# nigme2_Crocodile.net
KiCad netlist of a schematic drawn in Altium Designer
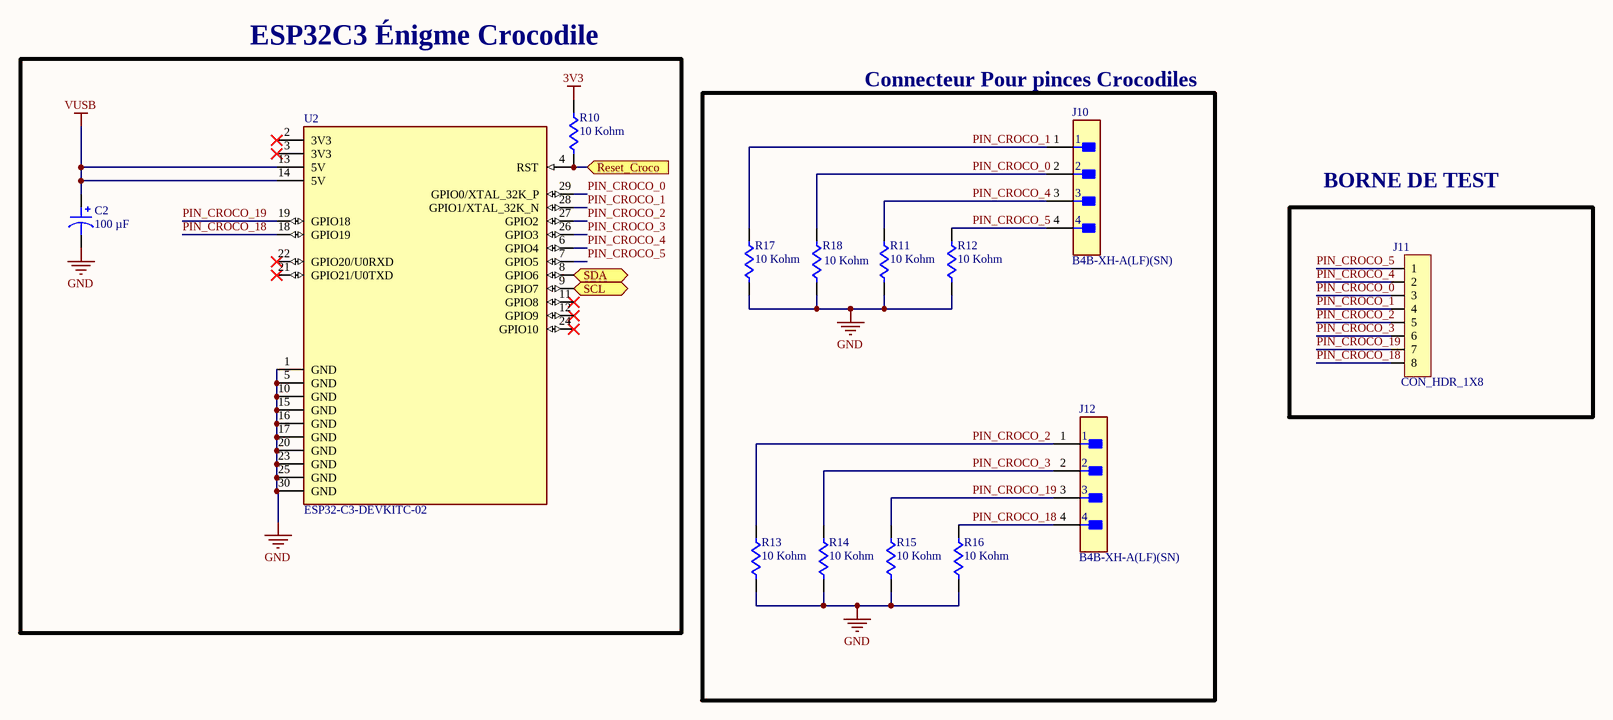
[diagram p0: Énigme2_Crocodile.SchDoc]

(export (version "E")
  (design (tool "Eeschema 10.0.6"))
  (components
    (comp (ref "C2")
      (value "100 µF")
      (footprint "CAP AL TH D8 L3.5 H12.5")
      (description "CAP ALUM 100UF 20% 50V RADIAL")
      (fields (field (name "PART NUMBER") "860020674015") (field (name "MANUFACTURER") "Würth Elektronik"))
      (libsource (lib "Celestial Altium Library - altium_library") (part "Polarised Capacitor"))
    )
    (comp (ref "J10")
      (value "B4B-XH-A(LF)(SN)")
      (footprint "FP-B4B-XH-A_LF_SN-MFG")
      (description "CONN HEADER VERT 4POS 2.5MM")
      (libsource (lib "Altium Content Vault") (part "299a8cea1bdcbc3624fe62c390fa72c"))
    )
    (comp (ref "J11")
      (value "CON_HDR_1X8")
      (footprint "CON_HDR_1x8")
      (description "CON - Header 1X8 pins, 100Mils - TH-8")
      (fields (field (name "SOURCE") "CEGEP_SHERBROOKE_TGE_LIBRARY.SchLib"))
      (libsource (lib "Cegep de Sherbrooke") (part "CON_HDR_1X8"))
    )
    (comp (ref "J12")
      (value "B4B-XH-A(LF)(SN)")
      (footprint "FP-B4B-XH-A_LF_SN-MFG")
      (description "CONN HEADER VERT 4POS 2.5MM")
      (libsource (lib "Altium Content Vault") (part "299a8cea1bdcbc3624fe62c390fa72c"))
    )
    (comp (ref "R10")
      (value "10 Kohm")
      (footprint "Res_Template")
      (description "Custom Semiconductor Resistor")
      (libsource (lib "Schlib1") (part "470 ohm"))
    )
    (comp (ref "R11")
      (value "10 Kohm")
      (footprint "Res_Template")
      (description "Custom Semiconductor Resistor")
      (libsource (lib "Schlib1") (part "470 ohm"))
    )
    (comp (ref "R12")
      (value "10 Kohm")
      (footprint "Res_Template")
      (description "Custom Semiconductor Resistor")
      (libsource (lib "Schlib1") (part "470 ohm"))
    )
    (comp (ref "R13")
      (value "10 Kohm")
      (footprint "Res_Template")
      (description "Custom Semiconductor Resistor")
      (libsource (lib "Schlib1") (part "470 ohm"))
    )
    (comp (ref "R14")
      (value "10 Kohm")
      (footprint "Res_Template")
      (description "Custom Semiconductor Resistor")
      (libsource (lib "Schlib1") (part "470 ohm"))
    )
    (comp (ref "R15")
      (value "10 Kohm")
      (footprint "Res_Template")
      (description "Custom Semiconductor Resistor")
      (libsource (lib "Schlib1") (part "470 ohm"))
    )
    (comp (ref "R16")
      (value "10 Kohm")
      (footprint "Res_Template")
      (description "Custom Semiconductor Resistor")
      (libsource (lib "Schlib1") (part "470 ohm"))
    )
    (comp (ref "R17")
      (value "10 Kohm")
      (footprint "Res_Template")
      (description "Custom Semiconductor Resistor")
      (libsource (lib "Schlib1") (part "470 ohm"))
    )
    (comp (ref "R18")
      (value "10 Kohm")
      (footprint "Res_Template")
      (description "Custom Semiconductor Resistor")
      (libsource (lib "Schlib1") (part "470 ohm"))
    )
    (comp (ref "U2")
      (value "ESP32-C3-DEVKITC-02")
      (footprint "XCVR_ESP32-C3-DEVKITC-02")
      (fields (field (name "MP") "ESP32-C3-DevKitC-02") (field (name "MF") "Espressif Systems"))
      (libsource (lib "ESP32-C3-DEVKITC-02") (part "ESP32-C3-DEVKITC-02"))
    )
  )
  (nets
    (net (code "1") (name "/PIN_CROCO_0") (class "Default")
      (node (ref "J10") (pin "2") (pinfunction "2_2") (pintype "passive"))
      (node (ref "J11") (pin "3") (pinfunction "3_3") (pintype "passive"))
      (node (ref "R18") (pin "2") (pinfunction "2_2") (pintype "passive"))
      (node (ref "U2") (pin "29") (pinfunction "GPIO0/XTAL_32K_P_29") (pintype "bidirectional"))
    )
    (net (code "2") (name "/PIN_CROCO_1") (class "Default")
      (node (ref "J10") (pin "1") (pinfunction "1_1") (pintype "passive"))
      (node (ref "J11") (pin "4") (pinfunction "4_4") (pintype "passive"))
      (node (ref "R17") (pin "2") (pinfunction "2_2") (pintype "passive"))
      (node (ref "U2") (pin "28") (pinfunction "GPIO1/XTAL_32K_N_28") (pintype "bidirectional"))
    )
    (net (code "3") (name "/PIN_CROCO_2") (class "Default")
      (node (ref "J11") (pin "5") (pinfunction "5_5") (pintype "passive"))
      (node (ref "J12") (pin "1") (pinfunction "1_1") (pintype "passive"))
      (node (ref "R13") (pin "2") (pinfunction "2_2") (pintype "passive"))
      (node (ref "U2") (pin "27") (pinfunction "GPIO2_27") (pintype "bidirectional"))
    )
    (net (code "4") (name "/PIN_CROCO_3") (class "Default")
      (node (ref "J11") (pin "6") (pinfunction "6_6") (pintype "passive"))
      (node (ref "J12") (pin "2") (pinfunction "2_2") (pintype "passive"))
      (node (ref "R14") (pin "2") (pinfunction "2_2") (pintype "passive"))
      (node (ref "U2") (pin "26") (pinfunction "GPIO3_26") (pintype "bidirectional"))
    )
    (net (code "5") (name "/PIN_CROCO_4") (class "Default")
      (node (ref "J10") (pin "3") (pinfunction "3_3") (pintype "passive"))
      (node (ref "J11") (pin "2") (pinfunction "2_2") (pintype "passive"))
      (node (ref "R11") (pin "2") (pinfunction "2_2") (pintype "passive"))
      (node (ref "U2") (pin "6") (pinfunction "GPIO4_6") (pintype "bidirectional"))
    )
    (net (code "6") (name "/PIN_CROCO_5") (class "Default")
      (node (ref "J10") (pin "4") (pinfunction "4_4") (pintype "passive"))
      (node (ref "J11") (pin "1") (pinfunction "1_1") (pintype "passive"))
      (node (ref "R12") (pin "2") (pinfunction "2_2") (pintype "passive"))
      (node (ref "U2") (pin "7") (pinfunction "GPIO5_7") (pintype "bidirectional"))
    )
    (net (code "7") (name "/PIN_CROCO_18") (class "Default")
      (node (ref "J11") (pin "8") (pinfunction "8_8") (pintype "passive"))
      (node (ref "J12") (pin "4") (pinfunction "4_4") (pintype "passive"))
      (node (ref "R16") (pin "2") (pinfunction "2_2") (pintype "passive"))
      (node (ref "U2") (pin "18") (pinfunction "GPIO19_18") (pintype "bidirectional"))
    )
    (net (code "8") (name "/PIN_CROCO_19") (class "Default")
      (node (ref "J11") (pin "7") (pinfunction "7_7") (pintype "passive"))
      (node (ref "J12") (pin "3") (pinfunction "3_3") (pintype "passive"))
      (node (ref "R15") (pin "2") (pinfunction "2_2") (pintype "passive"))
      (node (ref "U2") (pin "19") (pinfunction "GPIO18_19") (pintype "bidirectional"))
    )
    (net (code "9") (name "/Reset_Croco") (class "Default")
      (node (ref "R10") (pin "1") (pinfunction "1_1") (pintype "passive"))
      (node (ref "U2") (pin "4") (pinfunction "RST_4") (pintype "input"))
    )
    (net (code "10") (name "/SCL") (class "Default")
      (node (ref "U2") (pin "9") (pinfunction "GPIO7_9") (pintype "bidirectional"))
    )
    (net (code "11") (name "/SDA") (class "Default")
      (node (ref "U2") (pin "8") (pinfunction "GPIO6_8") (pintype "bidirectional"))
    )
    (net (code "12") (name "3V3") (class "Default")
      (node (ref "R10") (pin "2") (pinfunction "2_2") (pintype "passive"))
    )
    (net (code "13") (name "GND") (class "Default")
      (node (ref "C2") (pin "2") (pinfunction "2_2") (pintype "passive"))
      (node (ref "R11") (pin "1") (pinfunction "1_1") (pintype "passive"))
      (node (ref "R12") (pin "1") (pinfunction "1_1") (pintype "passive"))
      (node (ref "R13") (pin "1") (pinfunction "1_1") (pintype "passive"))
      (node (ref "R14") (pin "1") (pinfunction "1_1") (pintype "passive"))
      (node (ref "R15") (pin "1") (pinfunction "1_1") (pintype "passive"))
      (node (ref "R16") (pin "1") (pinfunction "1_1") (pintype "passive"))
      (node (ref "R17") (pin "1") (pinfunction "1_1") (pintype "passive"))
      (node (ref "R18") (pin "1") (pinfunction "1_1") (pintype "passive"))
      (node (ref "U2") (pin "1") (pinfunction "GND_1") (pintype "power_in"))
      (node (ref "U2") (pin "10") (pinfunction "GND_10") (pintype "power_in"))
      (node (ref "U2") (pin "15") (pinfunction "GND_15") (pintype "power_in"))
      (node (ref "U2") (pin "16") (pinfunction "GND_16") (pintype "power_in"))
      (node (ref "U2") (pin "17") (pinfunction "GND_17") (pintype "power_in"))
      (node (ref "U2") (pin "20") (pinfunction "GND_20") (pintype "power_in"))
      (node (ref "U2") (pin "23") (pinfunction "GND_23") (pintype "power_in"))
      (node (ref "U2") (pin "25") (pinfunction "GND_25") (pintype "power_in"))
      (node (ref "U2") (pin "30") (pinfunction "GND_30") (pintype "power_in"))
      (node (ref "U2") (pin "5") (pinfunction "GND_5") (pintype "power_in"))
    )
    (net (code "14") (name "VUSB") (class "Default")
      (node (ref "C2") (pin "1") (pinfunction "1_1") (pintype "passive"))
      (node (ref "U2") (pin "13") (pinfunction "5V_13") (pintype "power_in"))
      (node (ref "U2") (pin "14") (pinfunction "5V_14") (pintype "power_in"))
    )
    (net (code "15") (name "unconnected-(U2-3V3-Pad2)") (class "Default")
      (node (ref "U2") (pin "2") (pinfunction "3V3_2") (pintype "power_in+no_connect"))
    )
    (net (code "16") (name "unconnected-(U2-3V3-Pad3)") (class "Default")
      (node (ref "U2") (pin "3") (pinfunction "3V3_3") (pintype "power_in+no_connect"))
    )
    (net (code "17") (name "unconnected-(U2-GPIO8-Pad11)") (class "Default")
      (node (ref "U2") (pin "11") (pinfunction "GPIO8_11") (pintype "bidirectional+no_connect"))
    )
    (net (code "18") (name "unconnected-(U2-GPIO9-Pad12)") (class "Default")
      (node (ref "U2") (pin "12") (pinfunction "GPIO9_12") (pintype "bidirectional+no_connect"))
    )
    (net (code "19") (name "unconnected-(U2-GPIO10-Pad24)") (class "Default")
      (node (ref "U2") (pin "24") (pinfunction "GPIO10_24") (pintype "bidirectional+no_connect"))
    )
    (net (code "20") (name "unconnected-(U2-GPIO20{slash}U0RXD-Pad22)") (class "Default")
      (node (ref "U2") (pin "22") (pinfunction "GPIO20/U0RXD_22") (pintype "bidirectional+no_connect"))
    )
    (net (code "21") (name "unconnected-(U2-GPIO21{slash}U0TXD-Pad21)") (class "Default")
      (node (ref "U2") (pin "21") (pinfunction "GPIO21/U0TXD_21") (pintype "bidirectional+no_connect"))
    )
  )
)
